# ProPrj_stm32__2026-07-06.net
KiCad netlist of a schematic drawn in EasyEDA Pro
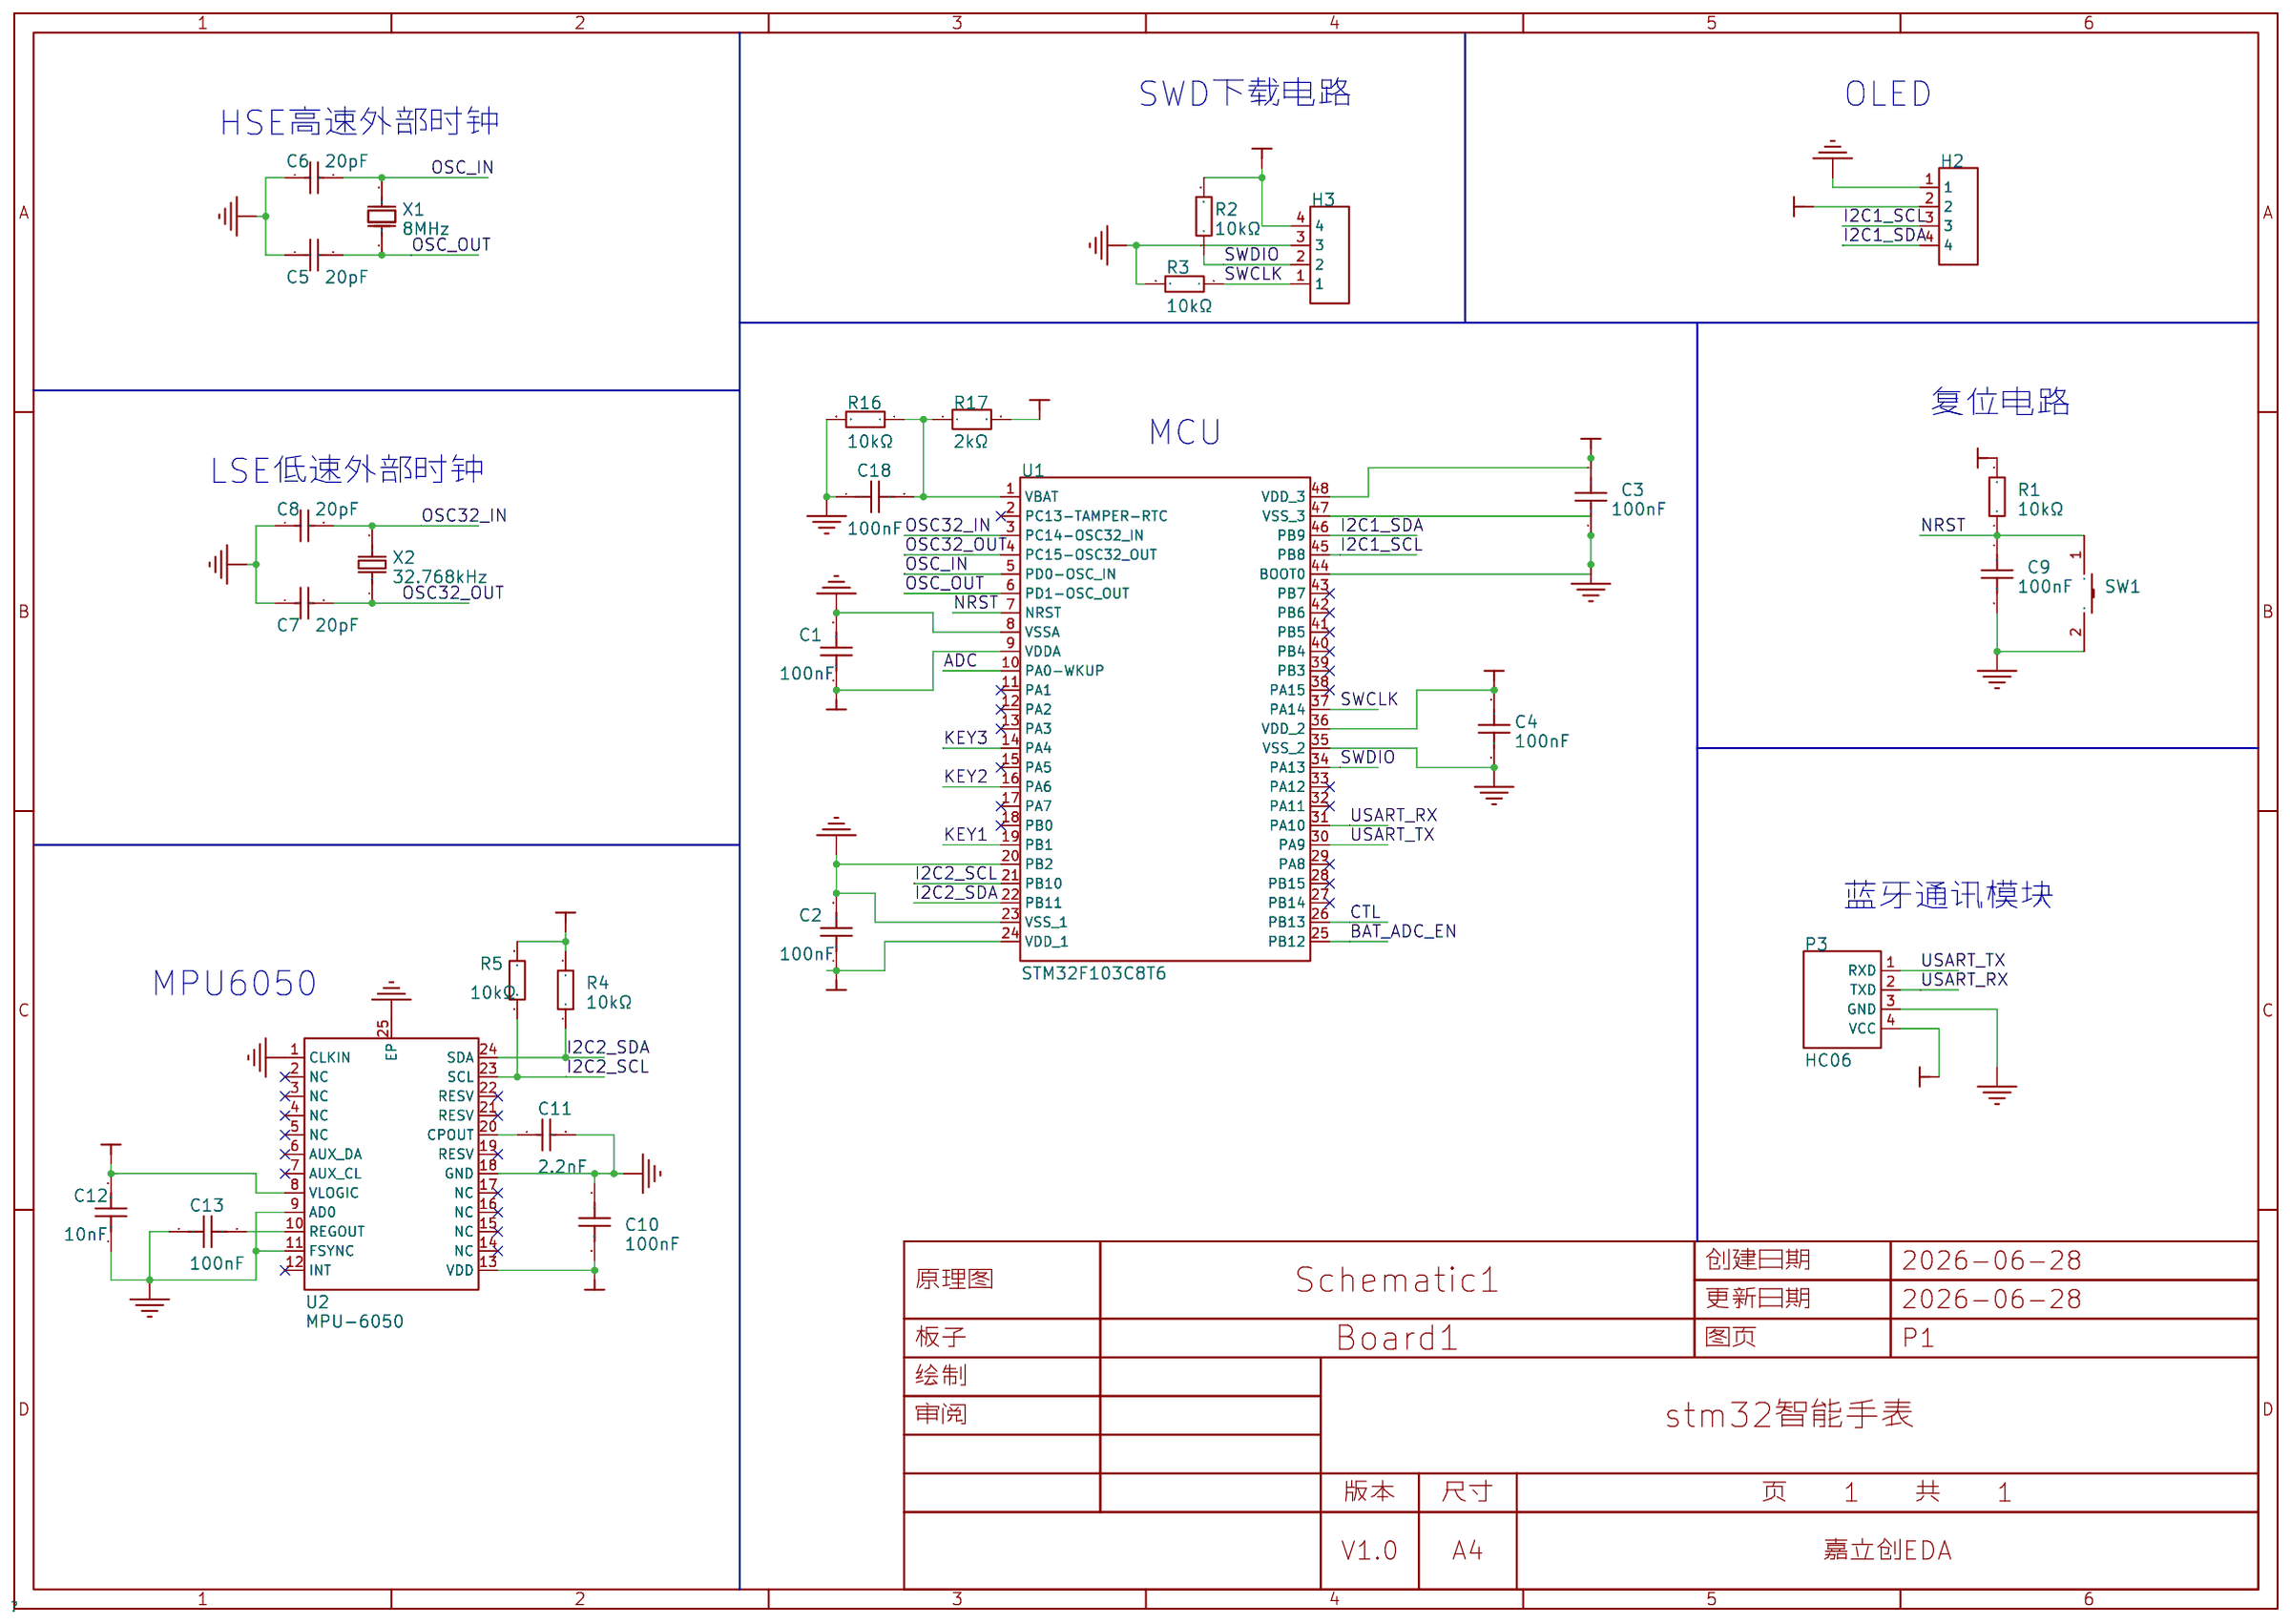
[diagram p0: P1]
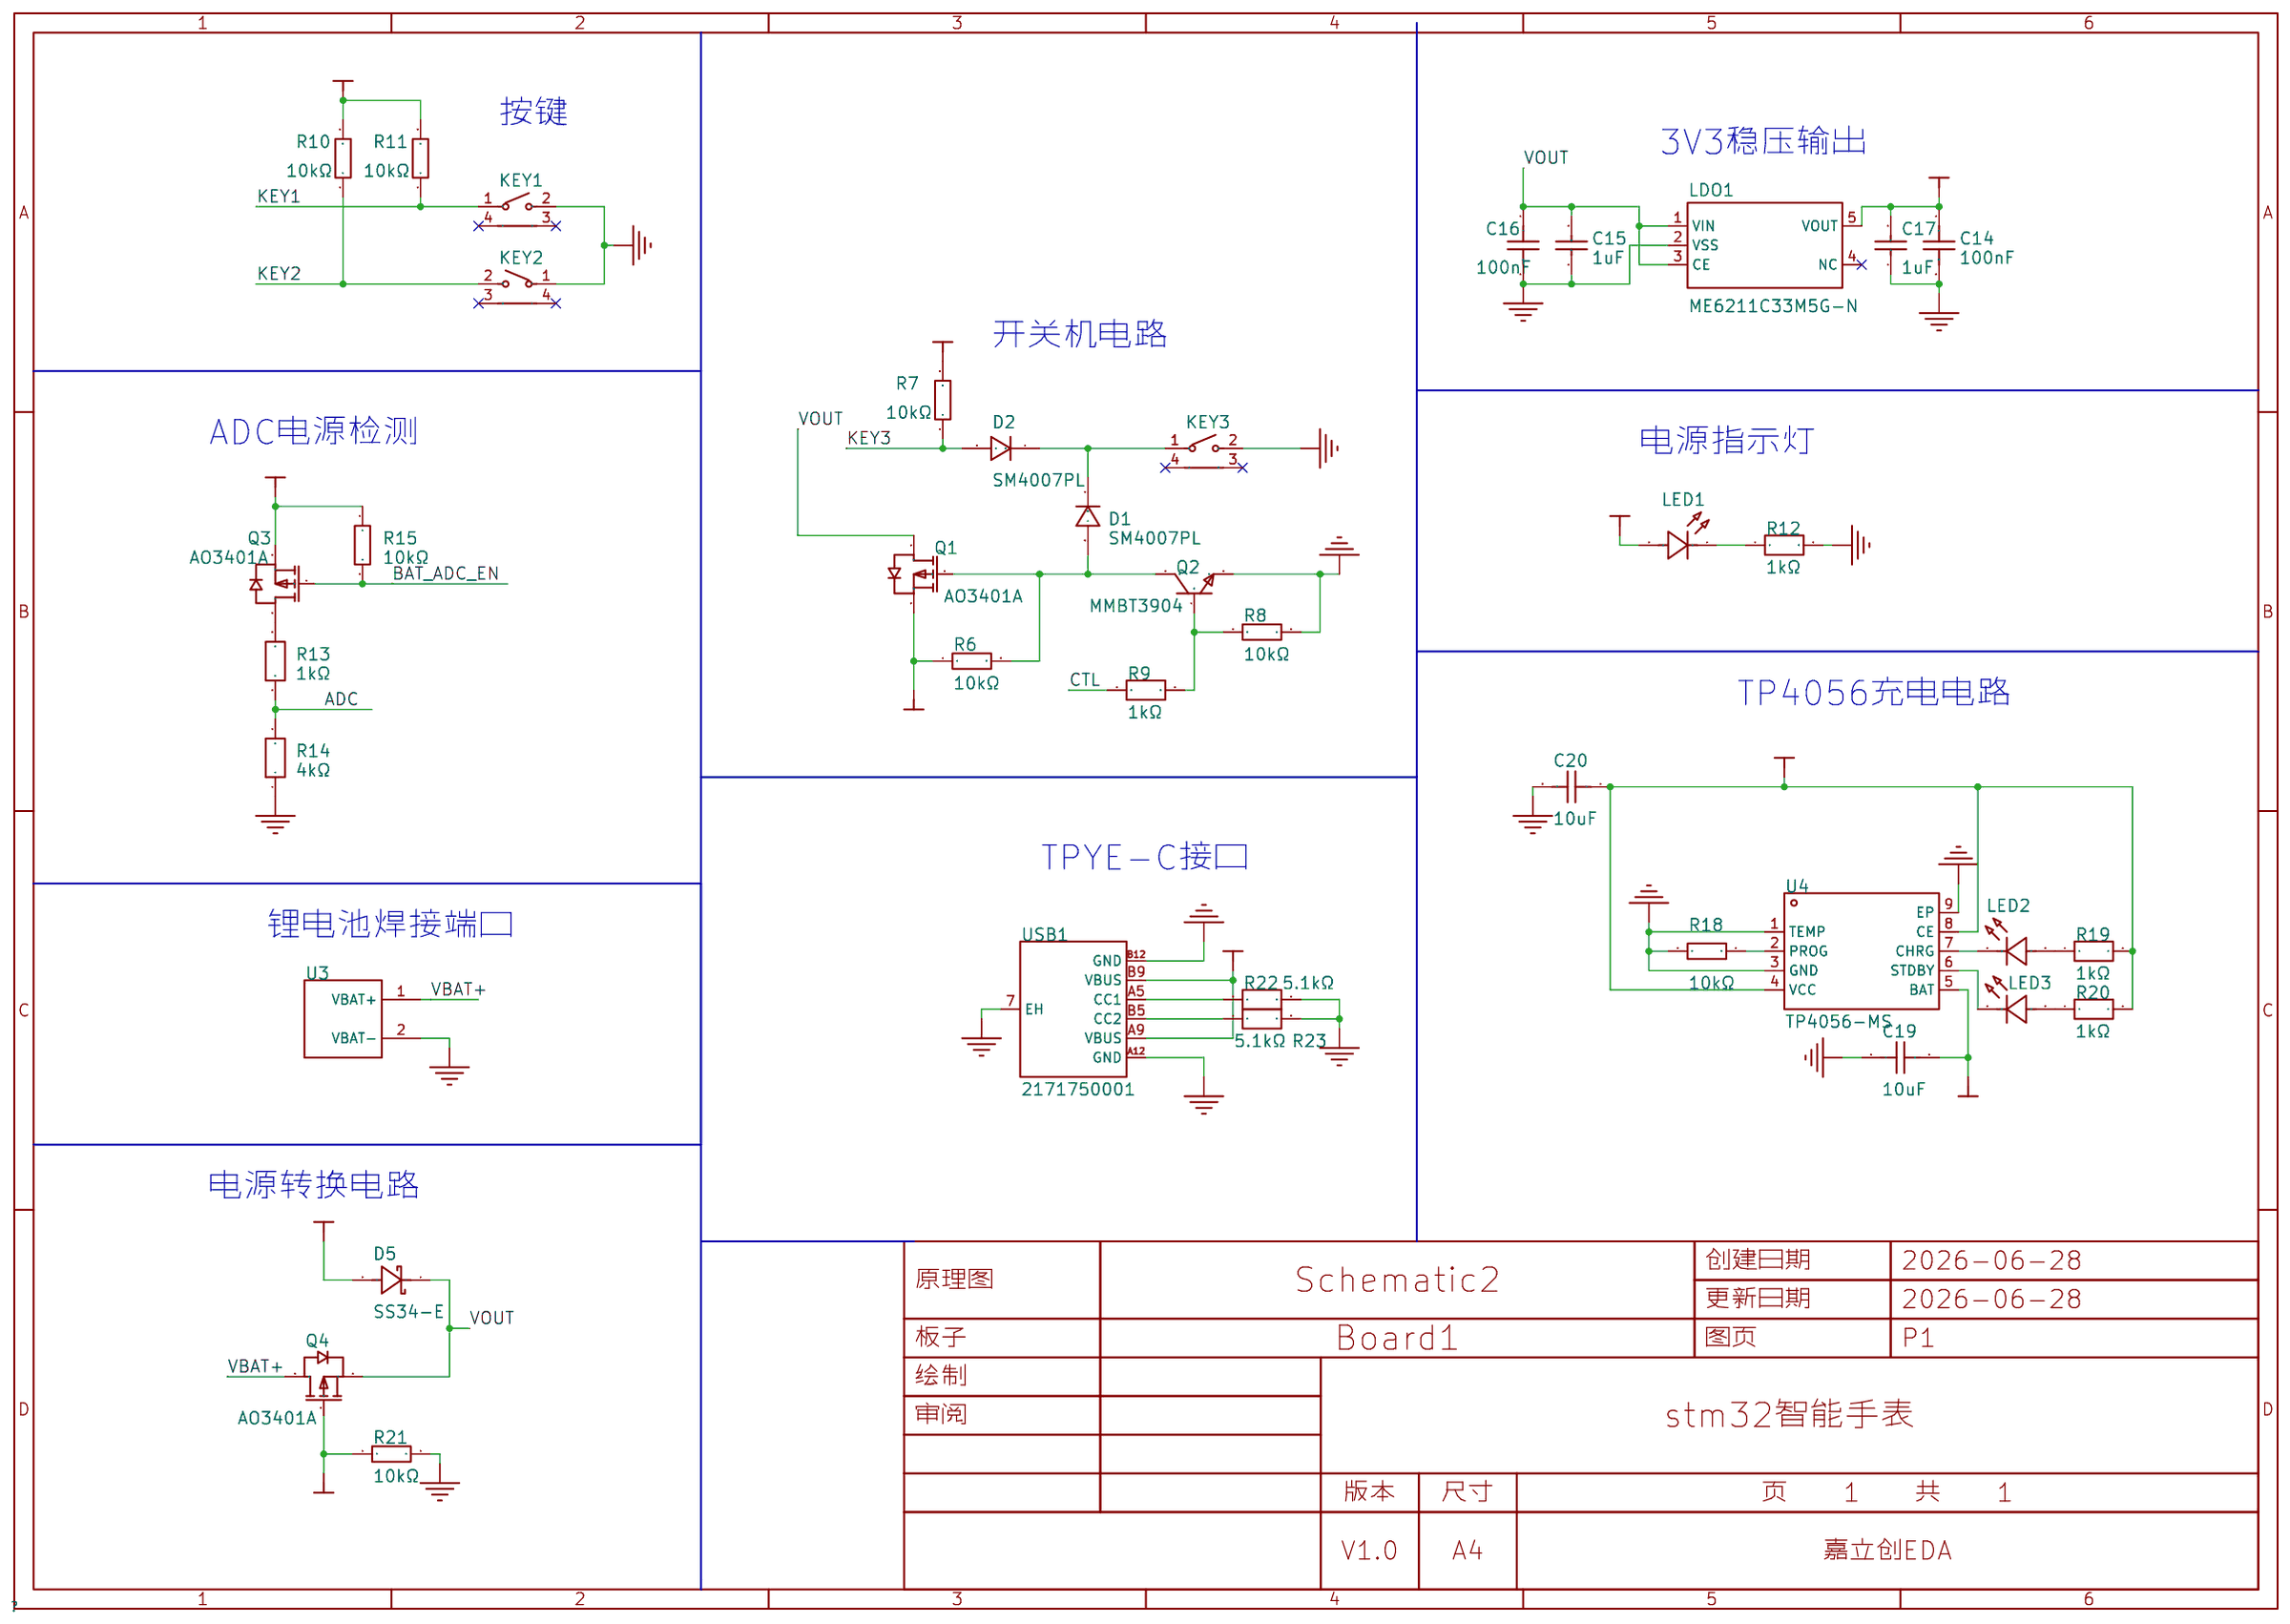
[diagram p1: P1_1]

(export (version "E")
  (design (tool "Eeschema 10.0.6"))
  (components
    (comp (ref "C1")
      (value "100nF")
      (footprint "easyedapro:C0603")
      (fields
        (field (name "Manufacturer Part") "CC0603KRX7R9BB104")
        (field (name "Manufacturer") "YAGEO(国巨)")
      )
      (libsource (lib "easyedapro") (part "CC0603KRX7R9BB104"))
    )
    (comp (ref "C2")
      (value "100nF")
      (footprint "easyedapro:C0603")
      (fields
        (field (name "Manufacturer Part") "CC0603KRX7R9BB104")
        (field (name "Manufacturer") "YAGEO(国巨)")
      )
      (libsource (lib "easyedapro") (part "CC0603KRX7R9BB104"))
    )
    (comp (ref "C3")
      (value "100nF")
      (footprint "easyedapro:C0603")
      (fields
        (field (name "Manufacturer Part") "CC0603KRX7R9BB104")
        (field (name "Manufacturer") "YAGEO(国巨)")
      )
      (libsource (lib "easyedapro") (part "CC0603KRX7R9BB104"))
    )
    (comp (ref "C4")
      (value "100nF")
      (footprint "easyedapro:C0603")
      (fields
        (field (name "Manufacturer Part") "CC0603KRX7R9BB104")
        (field (name "Manufacturer") "YAGEO(国巨)")
      )
      (libsource (lib "easyedapro") (part "CC0603KRX7R9BB104"))
    )
    (comp (ref "C5")
      (value "20pF")
      (footprint "easyedapro:C0603")
      (fields
        (field (name "Manufacturer Part") "CL10C200JB8NNNC")
        (field (name "Manufacturer") "SAMSUNG(三星)")
      )
      (libsource (lib "easyedapro") (part "CL10C200JB8NNNC"))
    )
    (comp (ref "C6")
      (value "20pF")
      (footprint "easyedapro:C0603")
      (fields
        (field (name "Manufacturer Part") "CL10C200JB8NNNC")
        (field (name "Manufacturer") "SAMSUNG(三星)")
      )
      (libsource (lib "easyedapro") (part "CL10C200JB8NNNC"))
    )
    (comp (ref "C7")
      (value "20pF")
      (footprint "easyedapro:C0603")
      (fields
        (field (name "Manufacturer Part") "CL10C200JB8NNNC")
        (field (name "Manufacturer") "SAMSUNG(三星)")
      )
      (libsource (lib "easyedapro") (part "CL10C200JB8NNNC"))
    )
    (comp (ref "C8")
      (value "20pF")
      (footprint "easyedapro:C0603")
      (fields
        (field (name "Manufacturer Part") "CL10C200JB8NNNC")
        (field (name "Manufacturer") "SAMSUNG(三星)")
      )
      (libsource (lib "easyedapro") (part "CL10C200JB8NNNC"))
    )
    (comp (ref "C9")
      (value "100nF")
      (footprint "easyedapro:C0603")
      (description "容值:100nF;精度:±10%;额定电压:50V;温度系数:X7R;")
      (fields
        (field (name "Manufacturer Part") "CC0603KRX7R9BB104")
        (field (name "Manufacturer") "YAGEO(国巨)")
      )
      (libsource (lib "easyedapro") (part "CC0603KRX7R9BB104"))
    )
    (comp (ref "C10")
      (value "100nF")
      (footprint "easyedapro:C0603")
      (description "容值:100nF;精度:±10%;额定电压:50V;温度系数:X7R;")
      (fields
        (field (name "Manufacturer Part") "CC0603KRX7R9BB104")
        (field (name "Manufacturer") "YAGEO(国巨)")
      )
      (libsource (lib "easyedapro") (part "CC0603KRX7R9BB104"))
    )
    (comp (ref "C11")
      (value "2.2nF")
      (footprint "easyedapro:C0603")
      (description "容值:2.2nF;精度:±10%;额定电压:50V;温度系数:X7R;")
      (fields (field (name "Manufacturer Part") "0603B222K500NT") (field (name "Manufacturer") "FH(风华)"))
      (libsource (lib "easyedapro") (part "0603B222K500NT"))
    )
    (comp (ref "C12")
      (value "10nF")
      (footprint "easyedapro:C0603")
      (description "容值:10nF;精度:±5%;额定电压:50V;材质(温度系数):C0G;")
      (fields
        (field (name "Manufacturer Part") "GRM1885C1H103JA01D")
        (field (name "Manufacturer") "muRata(村田)")
      )
      (libsource (lib "easyedapro") (part "GRM1885C1H103JA01D"))
    )
    (comp (ref "C13")
      (value "100nF")
      (footprint "easyedapro:C0603")
      (description "容值:100nF;精度:±10%;额定电压:50V;温度系数:X7R;")
      (fields
        (field (name "Manufacturer Part") "CC0603KRX7R9BB104")
        (field (name "Manufacturer") "YAGEO(国巨)")
      )
      (libsource (lib "easyedapro") (part "CC0603KRX7R9BB104"))
    )
    (comp (ref "C18")
      (value "100nF")
      (footprint "easyedapro:C0603")
      (fields
        (field (name "Manufacturer Part") "CC0603KRX7R9BB104")
        (field (name "Manufacturer") "YAGEO(国巨)")
      )
      (libsource (lib "easyedapro") (part "CC0603KRX7R9BB104"))
    )
    (comp (ref "H2")
      (value "HC-PM254-5.0H-1x4PZ-02A")
      (footprint "easyedapro:HDR-TH_4P-P2.54-V-F")
      (fields (field (name "Manufacturer") "HC(虹成电子)"))
      (libsource (lib "easyedapro") (part "HC-PM254-5.0H-1X4PZ-02A"))
    )
    (comp (ref "H3")
      (value "PZ2.54R-1X4P-H25")
      (footprint "easyedapro:HDR-TH_4P-P2.54-H-M-W10.0")
      (fields (field (name "Manufacturer") "JXTCONN(聚兴泰)"))
      (libsource (lib "easyedapro") (part "PZ2.54R-1X4P-H25"))
    )
    (comp (ref "P3")
      (value "HC06")
      (footprint "easyedapro:HC06")
      (libsource (lib "easyedapro") (part "HC06"))
    )
    (comp (ref "R1")
      (value "10kΩ")
      (footprint "easyedapro:R0603")
      (description "电阻类型:薄膜电阻;阻值:10kΩ;精度:±0.1%;功率:100mW;工作电压:75V;温度系数:±25ppm/℃;")
      (fields (field (name "Manufacturer Part") "RT0603BRD0710KL") (field (name "Manufacturer") "YAGEO(国巨)"))
      (libsource (lib "easyedapro") (part "RT0603BRD0710KL"))
    )
    (comp (ref "R2")
      (value "10kΩ")
      (footprint "easyedapro:R0603")
      (fields (field (name "Manufacturer Part") "RT0603BRD0710KL") (field (name "Manufacturer") "YAGEO(国巨)"))
      (libsource (lib "easyedapro") (part "RT0603BRD0710KL"))
    )
    (comp (ref "R3")
      (value "10kΩ")
      (footprint "easyedapro:R0603")
      (fields (field (name "Manufacturer Part") "RT0603BRD0710KL") (field (name "Manufacturer") "YAGEO(国巨)"))
      (libsource (lib "easyedapro") (part "RT0603BRD0710KL"))
    )
    (comp (ref "R4")
      (value "10kΩ")
      (footprint "easyedapro:R0603")
      (description "电阻类型:薄膜电阻;阻值:10kΩ;精度:±0.1%;功率:100mW;工作电压:75V;温度系数:±25ppm/℃;")
      (fields (field (name "Manufacturer Part") "RT0603BRD0710KL") (field (name "Manufacturer") "YAGEO(国巨)"))
      (libsource (lib "easyedapro") (part "RT0603BRD0710KL"))
    )
    (comp (ref "R5")
      (value "10kΩ")
      (footprint "easyedapro:R0603")
      (description "电阻类型:薄膜电阻;阻值:10kΩ;精度:±0.1%;功率:100mW;工作电压:75V;温度系数:±25ppm/℃;")
      (fields (field (name "Manufacturer Part") "RT0603BRD0710KL") (field (name "Manufacturer") "YAGEO(国巨)"))
      (libsource (lib "easyedapro") (part "RT0603BRD0710KL"))
    )
    (comp (ref "R16")
      (value "10kΩ")
      (footprint "easyedapro:R0603")
      (fields (field (name "Manufacturer Part") "RT0603BRD0710KL") (field (name "Manufacturer") "YAGEO(国巨)"))
      (libsource (lib "easyedapro") (part "RT0603BRD0710KL"))
    )
    (comp (ref "R17")
      (value "2kΩ")
      (footprint "easyedapro:R0603")
      (fields (field (name "Manufacturer Part") "FRC0603F2001TS") (field (name "Manufacturer") "FOJAN(富捷)"))
      (libsource (lib "easyedapro") (part "FRC0603F2001TS"))
    )
    (comp (ref "SW1")
      (value "TS-1101-C-W")
      (footprint "easyedapro:SW-SMD_L6.0-W3.3-LS8.0_TS-1101-C-W")
      (fields (field (name "Manufacturer") "XKB Connection(中国星坤)"))
      (libsource (lib "easyedapro") (part "TS-1101-C-W"))
    )
    (comp (ref "U1")
      (value "STM32F103C8T6")
      (footprint "easyedapro:LQFP-48_L7.0-W7.0-P0.50-LS9.0-BL")
      (fields (field (name "Manufacturer") "ST(意法半导体)"))
      (libsource (lib "easyedapro") (part "STM32F103C8T6"))
    )
    (comp (ref "U2")
      (value "MPU-6050")
      (footprint "easyedapro:QFN-24_L4.0-W4.0-P0.50-BL-EP2.7")
      (description "传感器类型:IMU(加速度计+陀螺仪);接口类型:I2C;")
      (fields (field (name "Manufacturer") "TDK InvenSense(应美盛)"))
      (libsource (lib "easyedapro") (part "MPU-6050_C24112"))
    )
    (comp (ref "X1")
      (value "8MHz")
      (footprint "easyedapro:CRYSTAL-SMD_L5.0-W3.2")
      (fields (field (name "Manufacturer Part") "X50328MSB2GI") (field (name "Manufacturer") "YXC(扬兴晶振)"))
      (libsource (lib "easyedapro") (part "X50328MSB2GI"))
    )
    (comp (ref "X2")
      (value "32.768kHz")
      (footprint "easyedapro:FC-135R_L3.2-W1.5")
      (fields (field (name "Manufacturer Part") "Q13FC13500004") (field (name "Manufacturer") "EPSON(爱普生)"))
      (libsource (lib "easyedapro") (part "Q13FC1350000400"))
    )
    (comp (ref "C14")
      (value "100nF")
      (footprint "easyedapro:C0603")
      (fields
        (field (name "Manufacturer Part") "CC0603KRX7R9BB104")
        (field (name "Manufacturer") "YAGEO(国巨)")
      )
      (libsource (lib "easyedapro") (part "CC0603KRX7R9BB104"))
    )
    (comp (ref "C15")
      (value "1uF")
      (footprint "easyedapro:C0603")
      (fields
        (field (name "Manufacturer Part") "CL10A105KO8NNNC")
        (field (name "Manufacturer") "SAMSUNG(三星)")
      )
      (libsource (lib "easyedapro") (part "CL10A105KO8NNNC"))
    )
    (comp (ref "C16")
      (value "100nF")
      (footprint "easyedapro:C0603")
      (fields
        (field (name "Manufacturer Part") "CC0603KRX7R9BB104")
        (field (name "Manufacturer") "YAGEO(国巨)")
      )
      (libsource (lib "easyedapro") (part "CC0603KRX7R9BB104"))
    )
    (comp (ref "C17")
      (value "1uF")
      (footprint "easyedapro:C0603")
      (fields
        (field (name "Manufacturer Part") "CL10A105KO8NNNC")
        (field (name "Manufacturer") "SAMSUNG(三星)")
      )
      (libsource (lib "easyedapro") (part "CL10A105KO8NNNC"))
    )
    (comp (ref "C19")
      (value "10uF")
      (footprint "easyedapro:C0603")
      (fields
        (field (name "Manufacturer Part") "CL10A106MQ8NNNC")
        (field (name "Manufacturer") "SAMSUNG(三星)")
      )
      (libsource (lib "easyedapro") (part "CL10A106MQ8NNNC"))
    )
    (comp (ref "C20")
      (value "10uF")
      (footprint "easyedapro:C0603")
      (fields
        (field (name "Manufacturer Part") "CL10A106MQ8NNNC")
        (field (name "Manufacturer") "SAMSUNG(三星)")
      )
      (libsource (lib "easyedapro") (part "CL10A106MQ8NNNC"))
    )
    (comp (ref "D1")
      (value "SM4007PL")
      (footprint "easyedapro:SOD-123F_L2.8-W1.8-LS3.7-RD")
      (fields (field (name "Manufacturer") "MDD(辰达半导体)"))
      (libsource (lib "easyedapro") (part "SM4007PL"))
    )
    (comp (ref "D2")
      (value "SM4007PL")
      (footprint "easyedapro:SOD-123F_L2.8-W1.8-LS3.7-RD")
      (fields (field (name "Manufacturer") "MDD(辰达半导体)"))
      (libsource (lib "easyedapro") (part "SM4007PL"))
    )
    (comp (ref "D5")
      (value "SS34-E")
      (footprint "easyedapro:SMA_L4.2-W2.6-LS5.0-RD")
      (fields (field (name "Manufacturer") "MDD(辰达半导体)"))
      (libsource (lib "easyedapro") (part "SS34-E"))
    )
    (comp (ref "KEY1")
      (value "GT-TC018A-H0375-L1")
      (footprint "easyedapro:SW-SMD_L4.7-W3.5-P3.35-EH")
      (fields (field (name "Manufacturer") "G-Switch(品赞)"))
      (libsource (lib "easyedapro") (part "GT-TC018A-H0375-L1"))
    )
    (comp (ref "KEY2")
      (value "GT-TC018A-H0375-L1")
      (footprint "easyedapro:SW-SMD_L4.7-W3.5-P3.35-EH")
      (fields (field (name "Manufacturer") "G-Switch(品赞)"))
      (libsource (lib "easyedapro") (part "GT-TC018A-H0375-L1"))
    )
    (comp (ref "KEY3")
      (value "GT-TC018A-H0375-L1")
      (footprint "easyedapro:SW-SMD_L4.7-W3.5-P3.35-EH")
      (fields (field (name "Manufacturer") "G-Switch(品赞)"))
      (libsource (lib "easyedapro") (part "GT-TC018A-H0375-L1"))
    )
    (comp (ref "LDO1")
      (value "ME6211C33M5G-N")
      (footprint "easyedapro:SOT-23-5_L3.0-W1.7-P0.95-LS2.8-BL")
      (fields (field (name "Manufacturer") "MICRONE(南京微盟)"))
      (libsource (lib "easyedapro") (part "ME6211C33M5G-N"))
    )
    (comp (ref "LED1")
      (value "XL-1608SURC-06")
      (footprint "easyedapro:LED0603-RD_RED")
      (fields (field (name "Manufacturer") "XINGLIGHT(成兴光)"))
      (libsource (lib "easyedapro") (part "XL-1608SURC-06"))
    )
    (comp (ref "LED2")
      (value "XL-1608SURC-06")
      (footprint "easyedapro:LED0603-RD_RED")
      (fields (field (name "Manufacturer") "XINGLIGHT(成兴光)"))
      (libsource (lib "easyedapro") (part "XL-1608SURC-06"))
    )
    (comp (ref "LED3")
      (value "F.0603.00025/P2-0603G1TS2-06T-002")
      (footprint "easyedapro:LED0603-RD_GREEN")
      (fields (field (name "Manufacturer") "TUOZHAN(拓展光电)"))
      (libsource (lib "easyedapro") (part "F.0603.00025/P2-0603G1TS2-06T-002"))
    )
    (comp (ref "Q1")
      (value "AO3401A")
      (footprint "easyedapro:SOT-23_L2.9-W1.3-P1.90-LS2.4-BR")
      (fields (field (name "Manufacturer") "UMW(友台半导体)"))
      (libsource (lib "easyedapro") (part "AO3401A_C347476"))
    )
    (comp (ref "Q2")
      (value "MMBT3904")
      (footprint "easyedapro:SOT-23-3_L2.9-W1.3-P1.90-LS2.4-BR")
      (fields (field (name "Manufacturer") "R+O(宏嘉诚)"))
      (libsource (lib "easyedapro") (part "MMBT3904_C7420353"))
    )
    (comp (ref "Q3")
      (value "AO3401A")
      (footprint "easyedapro:SOT-23_L2.9-W1.3-P1.90-LS2.4-BR")
      (fields (field (name "Manufacturer") "UMW(友台半导体)"))
      (libsource (lib "easyedapro") (part "AO3401A_C347476"))
    )
    (comp (ref "Q4")
      (value "AO3401A")
      (footprint "easyedapro:SOT-23_L2.9-W1.3-P1.90-LS2.4-BR")
      (fields (field (name "Manufacturer") "UMW(友台半导体)"))
      (libsource (lib "easyedapro") (part "AO3401A_C347476"))
    )
    (comp (ref "R6")
      (value "10kΩ")
      (footprint "easyedapro:R0603")
      (fields (field (name "Manufacturer Part") "RT0603BRD0710KL") (field (name "Manufacturer") "YAGEO(国巨)"))
      (libsource (lib "easyedapro") (part "RT0603BRD0710KL"))
    )
    (comp (ref "R7")
      (value "10kΩ")
      (footprint "easyedapro:R0603")
      (fields (field (name "Manufacturer Part") "RT0603BRD0710KL") (field (name "Manufacturer") "YAGEO(国巨)"))
      (libsource (lib "easyedapro") (part "RT0603BRD0710KL"))
    )
    (comp (ref "R8")
      (value "10kΩ")
      (footprint "easyedapro:R0603")
      (fields (field (name "Manufacturer Part") "RT0603BRD0710KL") (field (name "Manufacturer") "YAGEO(国巨)"))
      (libsource (lib "easyedapro") (part "RT0603BRD0710KL"))
    )
    (comp (ref "R9")
      (value "1kΩ")
      (footprint "easyedapro:R0603")
      (fields (field (name "Manufacturer Part") "FRC0603F1001TS") (field (name "Manufacturer") "FOJAN(富捷)"))
      (libsource (lib "easyedapro") (part "FRC0603F1001TS"))
    )
    (comp (ref "R10")
      (value "10kΩ")
      (footprint "easyedapro:R0603")
      (fields (field (name "Manufacturer Part") "RT0603BRD0710KL") (field (name "Manufacturer") "YAGEO(国巨)"))
      (libsource (lib "easyedapro") (part "RT0603BRD0710KL"))
    )
    (comp (ref "R11")
      (value "10kΩ")
      (footprint "easyedapro:R0603")
      (fields (field (name "Manufacturer Part") "RT0603BRD0710KL") (field (name "Manufacturer") "YAGEO(国巨)"))
      (libsource (lib "easyedapro") (part "RT0603BRD0710KL"))
    )
    (comp (ref "R12")
      (value "1kΩ")
      (footprint "easyedapro:R0603")
      (fields (field (name "Manufacturer Part") "FRC0603F1001TS") (field (name "Manufacturer") "FOJAN(富捷)"))
      (libsource (lib "easyedapro") (part "FRC0603F1001TS"))
    )
    (comp (ref "R13")
      (value "1kΩ")
      (footprint "easyedapro:R0603")
      (fields (field (name "Manufacturer Part") "FRC0603F1001TS") (field (name "Manufacturer") "FOJAN(富捷)"))
      (libsource (lib "easyedapro") (part "FRC0603F1001TS"))
    )
    (comp (ref "R14")
      (value "4kΩ")
      (footprint "easyedapro:R0603")
      (fields (field (name "Manufacturer Part") "ARG03FTC4001N") (field (name "Manufacturer") "Viking(光颉)"))
      (libsource (lib "easyedapro") (part "ARG03FTC4001N"))
    )
    (comp (ref "R15")
      (value "10kΩ")
      (footprint "easyedapro:R0603")
      (fields (field (name "Manufacturer Part") "RT0603BRD0710KL") (field (name "Manufacturer") "YAGEO(国巨)"))
      (libsource (lib "easyedapro") (part "RT0603BRD0710KL"))
    )
    (comp (ref "R18")
      (value "10kΩ")
      (footprint "easyedapro:R0603")
      (fields (field (name "Manufacturer Part") "RT0603BRD0710KL") (field (name "Manufacturer") "YAGEO(国巨)"))
      (libsource (lib "easyedapro") (part "RT0603BRD0710KL"))
    )
    (comp (ref "R19")
      (value "1kΩ")
      (footprint "easyedapro:R0603")
      (fields (field (name "Manufacturer Part") "FRC0603F1001TS") (field (name "Manufacturer") "FOJAN(富捷)"))
      (libsource (lib "easyedapro") (part "FRC0603F1001TS"))
    )
    (comp (ref "R20")
      (value "1kΩ")
      (footprint "easyedapro:R0603")
      (fields (field (name "Manufacturer Part") "FRC0603F1001TS") (field (name "Manufacturer") "FOJAN(富捷)"))
      (libsource (lib "easyedapro") (part "FRC0603F1001TS"))
    )
    (comp (ref "R21")
      (value "10kΩ")
      (footprint "easyedapro:R0603")
      (fields (field (name "Manufacturer Part") "RT0603BRD0710KL") (field (name "Manufacturer") "YAGEO(国巨)"))
      (libsource (lib "easyedapro") (part "RT0603BRD0710KL"))
    )
    (comp (ref "R22")
      (value "5.1kΩ")
      (footprint "easyedapro:R0603")
      (fields (field (name "Manufacturer Part") "FRC0603F5101TS") (field (name "Manufacturer") "FOJAN(富捷)"))
      (libsource (lib "easyedapro") (part "FRC0603F5101TS"))
    )
    (comp (ref "R23")
      (value "5.1kΩ")
      (footprint "easyedapro:R0603")
      (fields (field (name "Manufacturer Part") "FRC0603F5101TS") (field (name "Manufacturer") "FOJAN(富捷)"))
      (libsource (lib "easyedapro") (part "FRC0603F5101TS"))
    )
    (comp (ref "U3") (value "~") (libsource (lib "easyedapro") (part "302530BAT")))
    (comp (ref "U4")
      (value "TP4056-MS")
      (footprint "easyedapro:SOP-8_L4.9-W3.9-P1.27-LS6.0-TL-EP")
      (fields (field (name "Manufacturer") "MSKSEMI(美森科)"))
      (libsource (lib "easyedapro") (part "TP4056-MS"))
    )
    (comp (ref "USB1")
      (value "2171750001")
      (footprint "easyedapro:TYPE-C-SMD_TYPE-C-6P_USB4125-GF-A-0190")
      (fields (field (name "Manufacturer") "MOLEX"))
      (libsource (lib "easyedapro") (part "2171750001"))
    )
  )
  (nets
    (net (code "1") (name "+5V") (class "Default")
      (node (ref "C20") (pin "1") (pinfunction "1_1") (pintype "unspecified"))
      (node (ref "D5") (pin "2") (pinfunction "+_2") (pintype "unspecified"))
      (node (ref "Q4") (pin "1") (pinfunction "G_1") (pintype "unspecified"))
      (node (ref "R19") (pin "2") (pinfunction "2_2") (pintype "unspecified"))
      (node (ref "R20") (pin "2") (pinfunction "2_2") (pintype "unspecified"))
      (node (ref "R21") (pin "1") (pinfunction "1_1") (pintype "input"))
      (node (ref "U4") (pin "4") (pinfunction "VCC_4") (pintype "unspecified"))
      (node (ref "U4") (pin "8") (pinfunction "CE_8") (pintype "unspecified"))
      (node (ref "USB1") (pin "A9") (pinfunction "VBUS_A9") (pintype "unspecified"))
      (node (ref "USB1") (pin "B9") (pinfunction "VBUS_B9") (pintype "unspecified"))
    )
    (net (code "2") (name "3V3") (class "Default")
      (node (ref "C1") (pin "1") (pinfunction "1_1") (pintype "unspecified"))
      (node (ref "C10") (pin "2") (pinfunction "2_2") (pintype "unspecified"))
      (node (ref "C12") (pin "2") (pinfunction "2_2") (pintype "unspecified"))
      (node (ref "C14") (pin "1") (pinfunction "1_1") (pintype "unspecified"))
      (node (ref "C17") (pin "2") (pinfunction "2_2") (pintype "input"))
      (node (ref "C2") (pin "1") (pinfunction "1_1") (pintype "unspecified"))
      (node (ref "C3") (pin "1") (pinfunction "1_1") (pintype "unspecified"))
      (node (ref "C4") (pin "1") (pinfunction "1_1") (pintype "unspecified"))
      (node (ref "H2") (pin "2") (pinfunction "2_2") (pintype "unspecified"))
      (node (ref "H3") (pin "4") (pinfunction "4_4") (pintype "unspecified"))
      (node (ref "LDO1") (pin "5") (pinfunction "VOUT_5") (pintype "unspecified"))
      (node (ref "LED1") (pin "2") (pinfunction "A_2") (pintype "unspecified"))
      (node (ref "P3") (pin "4") (pinfunction "VCC_4") (pintype "unspecified"))
      (node (ref "R1") (pin "2") (pinfunction "2_2") (pintype "input"))
      (node (ref "R10") (pin "2") (pinfunction "2_2") (pintype "input"))
      (node (ref "R11") (pin "2") (pinfunction "2_2") (pintype "input"))
      (node (ref "R2") (pin "2") (pinfunction "2_2") (pintype "input"))
      (node (ref "R4") (pin "2") (pinfunction "2_2") (pintype "input"))
      (node (ref "R5") (pin "2") (pinfunction "2_2") (pintype "input"))
      (node (ref "R7") (pin "2") (pinfunction "2_2") (pintype "input"))
      (node (ref "U1") (pin "24") (pinfunction "VDD_1_24") (pintype "unspecified"))
      (node (ref "U1") (pin "36") (pinfunction "VDD_2_36") (pintype "unspecified"))
      (node (ref "U1") (pin "48") (pinfunction "VDD_3_48") (pintype "unspecified"))
      (node (ref "U1") (pin "9") (pinfunction "VDDA_9") (pintype "unspecified"))
      (node (ref "U2") (pin "13") (pinfunction "VDD_13") (pintype "unspecified"))
      (node (ref "U2") (pin "8") (pinfunction "VLOGIC_8") (pintype "unspecified"))
    )
    (net (code "3") (name "ADC") (class "Default")
      (node (ref "R13") (pin "1") (pinfunction "1_1") (pintype "unspecified"))
      (node (ref "R14") (pin "2") (pinfunction "2_2") (pintype "unspecified"))
      (node (ref "U1") (pin "10") (pinfunction "PA0-WKUP_10") (pintype "unspecified"))
    )
    (net (code "4") (name "BAT_ADC_EN") (class "Default")
      (node (ref "Q3") (pin "1") (pinfunction "G_1") (pintype "unspecified"))
      (node (ref "R15") (pin "2") (pinfunction "2_2") (pintype "input"))
      (node (ref "U1") (pin "25") (pinfunction "PB12_25") (pintype "unspecified"))
    )
    (net (code "5") (name "CTL") (class "Default")
      (node (ref "R9") (pin "1") (pinfunction "1_1") (pintype "unspecified"))
      (node (ref "U1") (pin "26") (pinfunction "PB13_26") (pintype "unspecified"))
    )
    (net (code "6") (name "GND") (class "Default")
      (node (ref "C1") (pin "2") (pinfunction "2_2") (pintype "unspecified"))
      (node (ref "C10") (pin "1") (pinfunction "1_1") (pintype "unspecified"))
      (node (ref "C11") (pin "2") (pinfunction "2_2") (pintype "input"))
      (node (ref "C12") (pin "1") (pinfunction "1_1") (pintype "unspecified"))
      (node (ref "C13") (pin "1") (pinfunction "1_1") (pintype "unspecified"))
      (node (ref "C14") (pin "2") (pinfunction "2_2") (pintype "unspecified"))
      (node (ref "C15") (pin "1") (pinfunction "1_1") (pintype "input"))
      (node (ref "C16") (pin "2") (pinfunction "2_2") (pintype "unspecified"))
      (node (ref "C17") (pin "1") (pinfunction "1_1") (pintype "input"))
      (node (ref "C18") (pin "1") (pinfunction "1_1") (pintype "unspecified"))
      (node (ref "C19") (pin "2") (pinfunction "2_2") (pintype "unspecified"))
      (node (ref "C2") (pin "2") (pinfunction "2_2") (pintype "unspecified"))
      (node (ref "C20") (pin "2") (pinfunction "2_2") (pintype "unspecified"))
      (node (ref "C3") (pin "2") (pinfunction "2_2") (pintype "unspecified"))
      (node (ref "C4") (pin "2") (pinfunction "2_2") (pintype "unspecified"))
      (node (ref "C5") (pin "1") (pinfunction "1_1") (pintype "input"))
      (node (ref "C6") (pin "1") (pinfunction "1_1") (pintype "input"))
      (node (ref "C7") (pin "1") (pinfunction "1_1") (pintype "input"))
      (node (ref "C8") (pin "1") (pinfunction "1_1") (pintype "input"))
      (node (ref "C9") (pin "2") (pinfunction "2_2") (pintype "unspecified"))
      (node (ref "H2") (pin "1") (pinfunction "1_1") (pintype "unspecified"))
      (node (ref "H3") (pin "3") (pinfunction "3_3") (pintype "unspecified"))
      (node (ref "KEY1") (pin "2") (pinfunction "2_2") (pintype "unspecified"))
      (node (ref "KEY2") (pin "1") (pinfunction "1_1") (pintype "unspecified"))
      (node (ref "KEY3") (pin "2") (pinfunction "2_2") (pintype "unspecified"))
      (node (ref "LDO1") (pin "2") (pinfunction "VSS_2") (pintype "unspecified"))
      (node (ref "P3") (pin "3") (pinfunction "GND_3") (pintype "unspecified"))
      (node (ref "Q2") (pin "2") (pinfunction "E_2") (pintype "unspecified"))
      (node (ref "R12") (pin "2") (pinfunction "2_2") (pintype "unspecified"))
      (node (ref "R14") (pin "1") (pinfunction "1_1") (pintype "unspecified"))
      (node (ref "R16") (pin "2") (pinfunction "2_2") (pintype "input"))
      (node (ref "R18") (pin "2") (pinfunction "2_2") (pintype "input"))
      (node (ref "R21") (pin "2") (pinfunction "2_2") (pintype "input"))
      (node (ref "R22") (pin "2") (pinfunction "2_2") (pintype "unspecified"))
      (node (ref "R23") (pin "2") (pinfunction "2_2") (pintype "unspecified"))
      (node (ref "R3") (pin "2") (pinfunction "2_2") (pintype "input"))
      (node (ref "R8") (pin "1") (pinfunction "1_1") (pintype "input"))
      (node (ref "SW1") (pin "2") (pinfunction "2_2") (pintype "unspecified"))
      (node (ref "U1") (pin "20") (pinfunction "PB2_20") (pintype "unspecified"))
      (node (ref "U1") (pin "23") (pinfunction "VSS_1_23") (pintype "unspecified"))
      (node (ref "U1") (pin "35") (pinfunction "VSS_2_35") (pintype "unspecified"))
      (node (ref "U1") (pin "44") (pinfunction "BOOT0_44") (pintype "unspecified"))
      (node (ref "U1") (pin "47") (pinfunction "VSS_3_47") (pintype "unspecified"))
      (node (ref "U1") (pin "8") (pinfunction "VSSA_8") (pintype "unspecified"))
      (node (ref "U2") (pin "1") (pinfunction "CLKIN_1") (pintype "unspecified"))
      (node (ref "U2") (pin "11") (pinfunction "FSYNC_11") (pintype "unspecified"))
      (node (ref "U2") (pin "18") (pinfunction "GND_18") (pintype "unspecified"))
      (node (ref "U2") (pin "25") (pinfunction "EP_25") (pintype "unspecified"))
      (node (ref "U2") (pin "9") (pinfunction "AD0_9") (pintype "unspecified"))
      (node (ref "U3") (pin "2") (pinfunction "VBAT-_2") (pintype "unspecified"))
      (node (ref "U4") (pin "1") (pinfunction "TEMP_1") (pintype "unspecified"))
      (node (ref "U4") (pin "3") (pinfunction "GND_3") (pintype "unspecified"))
      (node (ref "U4") (pin "9") (pinfunction "EP_9") (pintype "unspecified"))
      (node (ref "USB1") (pin "7") (pinfunction "EH_7") (pintype "unspecified"))
      (node (ref "USB1") (pin "A12") (pinfunction "GND_A12") (pintype "unspecified"))
      (node (ref "USB1") (pin "B12") (pinfunction "GND_B12") (pintype "unspecified"))
    )
    (net (code "7") (name "I2C1_SCL") (class "Default")
      (node (ref "H2") (pin "3") (pinfunction "3_3") (pintype "unspecified"))
      (node (ref "U1") (pin "45") (pinfunction "PB8_45") (pintype "unspecified"))
    )
    (net (code "8") (name "I2C1_SDA") (class "Default")
      (node (ref "H2") (pin "4") (pinfunction "4_4") (pintype "unspecified"))
      (node (ref "U1") (pin "46") (pinfunction "PB9_46") (pintype "unspecified"))
    )
    (net (code "9") (name "I2C2_SCL") (class "Default")
      (node (ref "R5") (pin "1") (pinfunction "1_1") (pintype "input"))
      (node (ref "U1") (pin "21") (pinfunction "PB10_21") (pintype "unspecified"))
      (node (ref "U2") (pin "23") (pinfunction "SCL_23") (pintype "unspecified"))
    )
    (net (code "10") (name "I2C2_SDA") (class "Default")
      (node (ref "R4") (pin "1") (pinfunction "1_1") (pintype "input"))
      (node (ref "U1") (pin "22") (pinfunction "PB11_22") (pintype "unspecified"))
      (node (ref "U2") (pin "24") (pinfunction "SDA_24") (pintype "unspecified"))
    )
    (net (code "11") (name "KEY1") (class "Default")
      (node (ref "KEY1") (pin "1") (pinfunction "1_1") (pintype "unspecified"))
      (node (ref "R11") (pin "1") (pinfunction "1_1") (pintype "input"))
      (node (ref "U1") (pin "19") (pinfunction "PB1_19") (pintype "unspecified"))
    )
    (net (code "12") (name "KEY2") (class "Default")
      (node (ref "KEY2") (pin "2") (pinfunction "2_2") (pintype "unspecified"))
      (node (ref "R10") (pin "1") (pinfunction "1_1") (pintype "input"))
      (node (ref "U1") (pin "16") (pinfunction "PA6_16") (pintype "unspecified"))
    )
    (net (code "13") (name "KEY3") (class "Default")
      (node (ref "D2") (pin "2") (pinfunction "A_2") (pintype "unspecified"))
      (node (ref "R7") (pin "1") (pinfunction "1_1") (pintype "input"))
      (node (ref "U1") (pin "14") (pinfunction "PA4_14") (pintype "unspecified"))
    )
    (net (code "14") (name "NRST") (class "Default")
      (node (ref "C9") (pin "1") (pinfunction "1_1") (pintype "unspecified"))
      (node (ref "R1") (pin "1") (pinfunction "1_1") (pintype "input"))
      (node (ref "SW1") (pin "1") (pinfunction "1_1") (pintype "unspecified"))
      (node (ref "U1") (pin "7") (pinfunction "NRST_7") (pintype "unspecified"))
    )
    (net (code "15") (name "Net-(D1-A)") (class "Default")
      (node (ref "D1") (pin "2") (pinfunction "A_2") (pintype "unspecified"))
      (node (ref "Q1") (pin "1") (pinfunction "G_1") (pintype "unspecified"))
      (node (ref "Q2") (pin "3") (pinfunction "C_3") (pintype "unspecified"))
      (node (ref "R6") (pin "2") (pinfunction "2_2") (pintype "input"))
    )
    (net (code "16") (name "Net-(D1-C)") (class "Default")
      (node (ref "D1") (pin "1") (pinfunction "C_1") (pintype "unspecified"))
      (node (ref "D2") (pin "1") (pinfunction "C_1") (pintype "unspecified"))
      (node (ref "KEY3") (pin "1") (pinfunction "1_1") (pintype "unspecified"))
    )
    (net (code "17") (name "Net-(LED1-K)") (class "Default")
      (node (ref "LED1") (pin "1") (pinfunction "K_1") (pintype "unspecified"))
      (node (ref "R12") (pin "1") (pinfunction "1_1") (pintype "unspecified"))
    )
    (net (code "18") (name "Net-(LED2-A)") (class "Default")
      (node (ref "LED2") (pin "2") (pinfunction "A_2") (pintype "unspecified"))
      (node (ref "R19") (pin "1") (pinfunction "1_1") (pintype "unspecified"))
    )
    (net (code "19") (name "Net-(LED2-K)") (class "Default")
      (node (ref "LED2") (pin "1") (pinfunction "K_1") (pintype "unspecified"))
      (node (ref "U4") (pin "7") (pinfunction "CHRG_7") (pintype "unspecified"))
    )
    (net (code "20") (name "Net-(LED3-A)") (class "Default")
      (node (ref "LED3") (pin "2") (pinfunction "A_2") (pintype "unspecified"))
      (node (ref "R20") (pin "1") (pinfunction "1_1") (pintype "unspecified"))
    )
    (net (code "21") (name "Net-(LED3-C)") (class "Default")
      (node (ref "LED3") (pin "1") (pinfunction "C_1") (pintype "unspecified"))
      (node (ref "U4") (pin "6") (pinfunction "STDBY_6") (pintype "unspecified"))
    )
    (net (code "22") (name "Net-(Q2-B)") (class "Default")
      (node (ref "Q2") (pin "1") (pinfunction "B_1") (pintype "unspecified"))
      (node (ref "R8") (pin "2") (pinfunction "2_2") (pintype "input"))
      (node (ref "R9") (pin "2") (pinfunction "2_2") (pintype "unspecified"))
    )
    (net (code "23") (name "Net-(Q3-D)") (class "Default")
      (node (ref "Q3") (pin "3") (pinfunction "D_3") (pintype "unspecified"))
      (node (ref "R13") (pin "2") (pinfunction "2_2") (pintype "unspecified"))
    )
    (net (code "24") (name "Net-(U1-VBAT)") (class "Default")
      (node (ref "C18") (pin "2") (pinfunction "2_2") (pintype "unspecified"))
      (node (ref "R16") (pin "1") (pinfunction "1_1") (pintype "input"))
      (node (ref "R17") (pin "1") (pinfunction "1_1") (pintype "unspecified"))
      (node (ref "U1") (pin "1") (pinfunction "VBAT_1") (pintype "unspecified"))
    )
    (net (code "25") (name "Net-(U2-CPOUT)") (class "Default")
      (node (ref "C11") (pin "1") (pinfunction "1_1") (pintype "input"))
      (node (ref "U2") (pin "20") (pinfunction "CPOUT_20") (pintype "unspecified"))
    )
    (net (code "26") (name "Net-(U2-REGOUT)") (class "Default")
      (node (ref "C13") (pin "2") (pinfunction "2_2") (pintype "unspecified"))
      (node (ref "U2") (pin "10") (pinfunction "REGOUT_10") (pintype "unspecified"))
    )
    (net (code "27") (name "Net-(U4-PROG)") (class "Default")
      (node (ref "R18") (pin "1") (pinfunction "1_1") (pintype "input"))
      (node (ref "U4") (pin "2") (pinfunction "PROG_2") (pintype "unspecified"))
    )
    (net (code "28") (name "Net-(USB1-CC1)") (class "Default")
      (node (ref "R22") (pin "1") (pinfunction "1_1") (pintype "unspecified"))
      (node (ref "USB1") (pin "A5") (pinfunction "CC1_A5") (pintype "unspecified"))
    )
    (net (code "29") (name "Net-(USB1-CC2)") (class "Default")
      (node (ref "R23") (pin "1") (pinfunction "1_1") (pintype "unspecified"))
      (node (ref "USB1") (pin "B5") (pinfunction "CC2_B5") (pintype "unspecified"))
    )
    (net (code "30") (name "OSC32_IN") (class "Default")
      (node (ref "C8") (pin "2") (pinfunction "2_2") (pintype "input"))
      (node (ref "U1") (pin "3") (pinfunction "PC14-OSC32_IN_3") (pintype "unspecified"))
      (node (ref "X2") (pin "2") (pinfunction "2_2") (pintype "unspecified"))
    )
    (net (code "31") (name "OSC32_OUT") (class "Default")
      (node (ref "C7") (pin "2") (pinfunction "2_2") (pintype "input"))
      (node (ref "U1") (pin "4") (pinfunction "PC15-OSC32_OUT_4") (pintype "unspecified"))
      (node (ref "X2") (pin "1") (pinfunction "1_1") (pintype "unspecified"))
    )
    (net (code "32") (name "OSC_IN") (class "Default")
      (node (ref "C6") (pin "2") (pinfunction "2_2") (pintype "input"))
      (node (ref "U1") (pin "5") (pinfunction "PD0-OSC_IN_5") (pintype "unspecified"))
      (node (ref "X1") (pin "2") (pinfunction "OSC2_2") (pintype "input"))
    )
    (net (code "33") (name "OSC_OUT") (class "Default")
      (node (ref "C5") (pin "2") (pinfunction "2_2") (pintype "input"))
      (node (ref "U1") (pin "6") (pinfunction "PD1-OSC_OUT_6") (pintype "unspecified"))
      (node (ref "X1") (pin "1") (pinfunction "OSC1_1") (pintype "input"))
    )
    (net (code "34") (name "SWCLK") (class "Default")
      (node (ref "H3") (pin "1") (pinfunction "1_1") (pintype "unspecified"))
      (node (ref "R3") (pin "1") (pinfunction "1_1") (pintype "input"))
      (node (ref "U1") (pin "37") (pinfunction "PA14_37") (pintype "unspecified"))
    )
    (net (code "35") (name "SWDIO") (class "Default")
      (node (ref "H3") (pin "2") (pinfunction "2_2") (pintype "unspecified"))
      (node (ref "R2") (pin "1") (pinfunction "1_1") (pintype "input"))
      (node (ref "U1") (pin "34") (pinfunction "PA13_34") (pintype "unspecified"))
    )
    (net (code "36") (name "USART_RX") (class "Default")
      (node (ref "P3") (pin "2") (pinfunction "TXD_2") (pintype "unspecified"))
      (node (ref "U1") (pin "31") (pinfunction "PA10_31") (pintype "unspecified"))
    )
    (net (code "37") (name "USART_TX") (class "Default")
      (node (ref "P3") (pin "1") (pinfunction "RXD_1") (pintype "unspecified"))
      (node (ref "U1") (pin "30") (pinfunction "PA9_30") (pintype "unspecified"))
    )
    (net (code "38") (name "VBAT+") (class "Default")
      (node (ref "C19") (pin "1") (pinfunction "1_1") (pintype "unspecified"))
      (node (ref "Q1") (pin "2") (pinfunction "S_2") (pintype "unspecified"))
      (node (ref "Q3") (pin "2") (pinfunction "S_2") (pintype "unspecified"))
      (node (ref "Q4") (pin "3") (pinfunction "D_3") (pintype "unspecified"))
      (node (ref "R15") (pin "1") (pinfunction "1_1") (pintype "input"))
      (node (ref "R17") (pin "2") (pinfunction "2_2") (pintype "unspecified"))
      (node (ref "R6") (pin "1") (pinfunction "1_1") (pintype "input"))
      (node (ref "U3") (pin "1") (pinfunction "VBAT+_1") (pintype "unspecified"))
      (node (ref "U4") (pin "5") (pinfunction "BAT_5") (pintype "unspecified"))
    )
    (net (code "39") (name "VOUT") (class "Default")
      (node (ref "C15") (pin "2") (pinfunction "2_2") (pintype "input"))
      (node (ref "C16") (pin "1") (pinfunction "1_1") (pintype "unspecified"))
      (node (ref "D5") (pin "1") (pinfunction "-_1") (pintype "unspecified"))
      (node (ref "LDO1") (pin "1") (pinfunction "VIN_1") (pintype "unspecified"))
      (node (ref "LDO1") (pin "3") (pinfunction "CE_3") (pintype "unspecified"))
      (node (ref "Q1") (pin "3") (pinfunction "D_3") (pintype "unspecified"))
      (node (ref "Q4") (pin "2") (pinfunction "S_2") (pintype "unspecified"))
    )
    (net (code "40") (name "unconnected-(KEY1-Pad3)") (class "Default")
      (node (ref "KEY1") (pin "3") (pinfunction "3_3") (pintype "unspecified+no_connect"))
    )
    (net (code "41") (name "unconnected-(KEY1-Pad4)") (class "Default")
      (node (ref "KEY1") (pin "4") (pinfunction "4_4") (pintype "unspecified+no_connect"))
    )
    (net (code "42") (name "unconnected-(KEY2-Pad3)") (class "Default")
      (node (ref "KEY2") (pin "3") (pinfunction "3_3") (pintype "unspecified+no_connect"))
    )
    (net (code "43") (name "unconnected-(KEY2-Pad4)") (class "Default")
      (node (ref "KEY2") (pin "4") (pinfunction "4_4") (pintype "unspecified+no_connect"))
    )
    (net (code "44") (name "unconnected-(KEY3-Pad3)") (class "Default")
      (node (ref "KEY3") (pin "3") (pinfunction "3_3") (pintype "unspecified+no_connect"))
    )
    (net (code "45") (name "unconnected-(KEY3-Pad4)") (class "Default")
      (node (ref "KEY3") (pin "4") (pinfunction "4_4") (pintype "unspecified+no_connect"))
    )
    (net (code "46") (name "unconnected-(LDO1-NC-Pad4)") (class "Default")
      (node (ref "LDO1") (pin "4") (pinfunction "NC_4") (pintype "unspecified+no_connect"))
    )
    (net (code "47") (name "unconnected-(U1-PA1-Pad11)") (class "Default")
      (node (ref "U1") (pin "11") (pinfunction "PA1_11") (pintype "unspecified+no_connect"))
    )
    (net (code "48") (name "unconnected-(U1-PA2-Pad12)") (class "Default")
      (node (ref "U1") (pin "12") (pinfunction "PA2_12") (pintype "unspecified+no_connect"))
    )
    (net (code "49") (name "unconnected-(U1-PA3-Pad13)") (class "Default")
      (node (ref "U1") (pin "13") (pinfunction "PA3_13") (pintype "unspecified+no_connect"))
    )
    (net (code "50") (name "unconnected-(U1-PA5-Pad15)") (class "Default")
      (node (ref "U1") (pin "15") (pinfunction "PA5_15") (pintype "unspecified+no_connect"))
    )
    (net (code "51") (name "unconnected-(U1-PA7-Pad17)") (class "Default")
      (node (ref "U1") (pin "17") (pinfunction "PA7_17") (pintype "unspecified+no_connect"))
    )
    (net (code "52") (name "unconnected-(U1-PA8-Pad29)") (class "Default")
      (node (ref "U1") (pin "29") (pinfunction "PA8_29") (pintype "unspecified+no_connect"))
    )
    (net (code "53") (name "unconnected-(U1-PA11-Pad32)") (class "Default")
      (node (ref "U1") (pin "32") (pinfunction "PA11_32") (pintype "unspecified+no_connect"))
    )
    (net (code "54") (name "unconnected-(U1-PA12-Pad33)") (class "Default")
      (node (ref "U1") (pin "33") (pinfunction "PA12_33") (pintype "unspecified+no_connect"))
    )
    (net (code "55") (name "unconnected-(U1-PA15-Pad38)") (class "Default")
      (node (ref "U1") (pin "38") (pinfunction "PA15_38") (pintype "unspecified+no_connect"))
    )
    (net (code "56") (name "unconnected-(U1-PB0-Pad18)") (class "Default")
      (node (ref "U1") (pin "18") (pinfunction "PB0_18") (pintype "unspecified+no_connect"))
    )
    (net (code "57") (name "unconnected-(U1-PB3-Pad39)") (class "Default")
      (node (ref "U1") (pin "39") (pinfunction "PB3_39") (pintype "unspecified+no_connect"))
    )
    (net (code "58") (name "unconnected-(U1-PB4-Pad40)") (class "Default")
      (node (ref "U1") (pin "40") (pinfunction "PB4_40") (pintype "unspecified+no_connect"))
    )
    (net (code "59") (name "unconnected-(U1-PB5-Pad41)") (class "Default")
      (node (ref "U1") (pin "41") (pinfunction "PB5_41") (pintype "unspecified+no_connect"))
    )
    (net (code "60") (name "unconnected-(U1-PB6-Pad42)") (class "Default")
      (node (ref "U1") (pin "42") (pinfunction "PB6_42") (pintype "unspecified+no_connect"))
    )
    (net (code "61") (name "unconnected-(U1-PB7-Pad43)") (class "Default")
      (node (ref "U1") (pin "43") (pinfunction "PB7_43") (pintype "unspecified+no_connect"))
    )
    (net (code "62") (name "unconnected-(U1-PB14-Pad27)") (class "Default")
      (node (ref "U1") (pin "27") (pinfunction "PB14_27") (pintype "unspecified+no_connect"))
    )
    (net (code "63") (name "unconnected-(U1-PB15-Pad28)") (class "Default")
      (node (ref "U1") (pin "28") (pinfunction "PB15_28") (pintype "unspecified+no_connect"))
    )
    (net (code "64") (name "unconnected-(U1-PC13-TAMPER-RTC-Pad2)") (class "Default")
      (node (ref "U1") (pin "2") (pinfunction "PC13-TAMPER-RTC_2") (pintype "unspecified+no_connect"))
    )
    (net (code "65") (name "unconnected-(U2-AUX_CL-Pad7)") (class "Default")
      (node (ref "U2") (pin "7") (pinfunction "AUX_CL_7") (pintype "unspecified+no_connect"))
    )
    (net (code "66") (name "unconnected-(U2-AUX_DA-Pad6)") (class "Default")
      (node (ref "U2") (pin "6") (pinfunction "AUX_DA_6") (pintype "unspecified+no_connect"))
    )
    (net (code "67") (name "unconnected-(U2-INT-Pad12)") (class "Default")
      (node (ref "U2") (pin "12") (pinfunction "INT_12") (pintype "unspecified+no_connect"))
    )
    (net (code "68") (name "unconnected-(U2-NC-Pad2)") (class "Default")
      (node (ref "U2") (pin "2") (pinfunction "NC_2") (pintype "unspecified+no_connect"))
    )
    (net (code "69") (name "unconnected-(U2-NC-Pad3)") (class "Default")
      (node (ref "U2") (pin "3") (pinfunction "NC_3") (pintype "unspecified+no_connect"))
    )
    (net (code "70") (name "unconnected-(U2-NC-Pad4)") (class "Default")
      (node (ref "U2") (pin "4") (pinfunction "NC_4") (pintype "unspecified+no_connect"))
    )
    (net (code "71") (name "unconnected-(U2-NC-Pad5)") (class "Default")
      (node (ref "U2") (pin "5") (pinfunction "NC_5") (pintype "unspecified+no_connect"))
    )
    (net (code "72") (name "unconnected-(U2-NC-Pad14)") (class "Default")
      (node (ref "U2") (pin "14") (pinfunction "NC_14") (pintype "unspecified+no_connect"))
    )
    (net (code "73") (name "unconnected-(U2-NC-Pad15)") (class "Default")
      (node (ref "U2") (pin "15") (pinfunction "NC_15") (pintype "unspecified+no_connect"))
    )
    (net (code "74") (name "unconnected-(U2-NC-Pad16)") (class "Default")
      (node (ref "U2") (pin "16") (pinfunction "NC_16") (pintype "unspecified+no_connect"))
    )
    (net (code "75") (name "unconnected-(U2-NC-Pad17)") (class "Default")
      (node (ref "U2") (pin "17") (pinfunction "NC_17") (pintype "unspecified+no_connect"))
    )
    (net (code "76") (name "unconnected-(U2-RESV-Pad19)") (class "Default")
      (node (ref "U2") (pin "19") (pinfunction "RESV_19") (pintype "unspecified+no_connect"))
    )
    (net (code "77") (name "unconnected-(U2-RESV-Pad21)") (class "Default")
      (node (ref "U2") (pin "21") (pinfunction "RESV_21") (pintype "unspecified+no_connect"))
    )
    (net (code "78") (name "unconnected-(U2-RESV-Pad22)") (class "Default")
      (node (ref "U2") (pin "22") (pinfunction "RESV_22") (pintype "unspecified+no_connect"))
    )
  )
)
